# Hoja_principal_Sumo_2024.net
KiCad netlist of a schematic drawn in Altium Designer
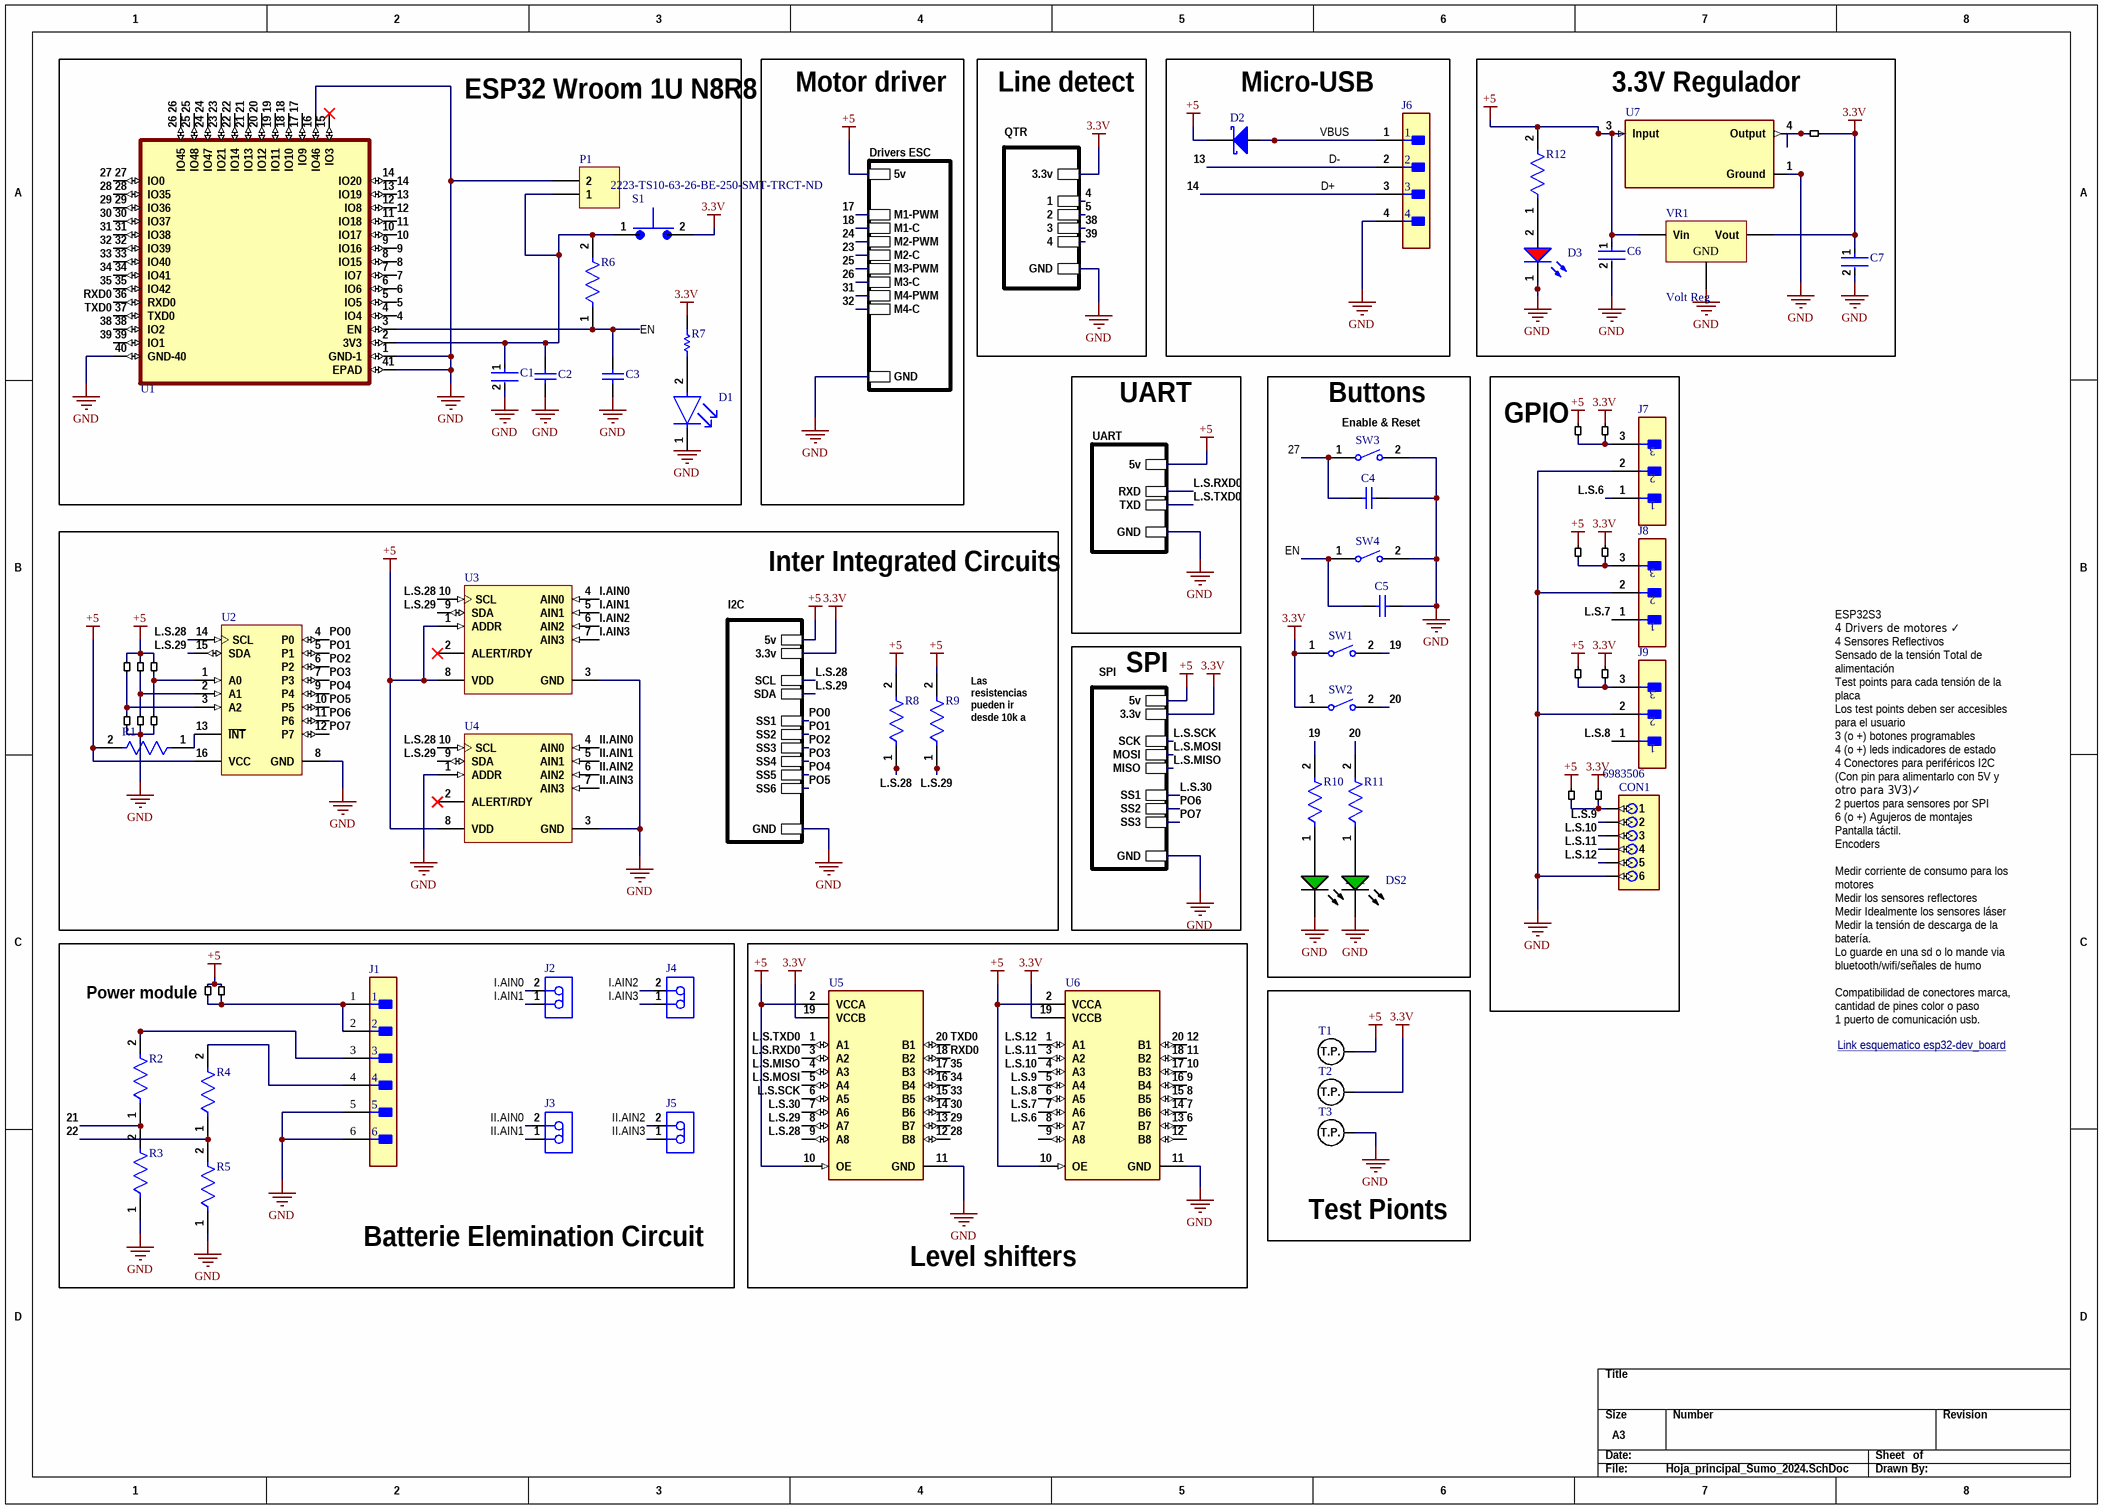
[diagram p0: Hoja_principal_Sumo_2024.SchDoc]

(export (version "E")
  (design (tool "Eeschema 10.0.6"))
  (components
    (comp (ref "C1")
      (value "TMK212BBJ106KG-T")
      (footprint "FP-0805-L_2_0_0_2-W_1_25-MFG")
      (description "Multilayer Ceramic Capacitor 10uF 25V X5R 10% SMD 0805 T/R")
      (fields (field (name "VOLTAGE") "16V") (field (name "TOLERANCE") "10%"))
      (libsource (lib "Altium Content Vault") (part "02cd4be3c70576c341d710602a673aa"))
    )
    (comp (ref "C2")
      (value "GRM21BR71H104KA01L")
      (footprint "CAPC2013X135X45ML10T25")
      (description "Chip Capacitor, 0.1 uF, +/- 10%, 50 V, -55 to 125 degC, 0805 (2012 Metric), RoHS, Tape and Reel")
      (fields (field (name "VOLTAGE") "50V") (field (name "TOLERANCE") "10%"))
      (libsource (lib "Altium Content Vault") (part "CAP-NP-2"))
    )
    (comp (ref "C3")
      (value "C0805C105K4PACTU")
      (footprint "CAPC2013X145X50LL20T25")
      (fields (field (name "MANUFACTURER") "Kemet"))
      (libsource (lib "Altium Content Vault") (part "CAP"))
    )
    (comp (ref "C4")
      (value "GRM21BR71H104KA01L")
      (footprint "CAPC2013X135X45ML10T25")
      (description "Chip Capacitor, 0.1 uF, +/- 10%, 50 V, -55 to 125 degC, 0805 (2012 Metric), RoHS, Tape and Reel")
      (fields (field (name "VOLTAGE") "50V") (field (name "TOLERANCE") "10%"))
      (libsource (lib "Altium Content Vault") (part "CAP-NP-2"))
    )
    (comp (ref "C5")
      (value "GRM21BR71H104KA01L")
      (footprint "CAPC2013X135X45ML10T25")
      (description "Chip Capacitor, 0.1 uF, +/- 10%, 50 V, -55 to 125 degC, 0805 (2012 Metric), RoHS, Tape and Reel")
      (fields (field (name "VOLTAGE") "50V") (field (name "TOLERANCE") "10%"))
      (libsource (lib "Altium Content Vault") (part "CAP-NP-2"))
    )
    (comp (ref "C6")
      (value "GRM31CR71A226KE15L")
      (footprint "FP-GRM31C-0_2-e0_3_0_8-MFG")
      (description "Chip Multilayer Ceramic Capacitors for General Purpose, 1206, 22uF, X7R, 15%, 10%, 10V")
      (fields (field (name "VOLTAGE") "10V") (field (name "TOLERANCE") "10%"))
      (libsource (lib "Altium Content Vault") (part "02cd4be3c70576c341d710602a673aa"))
    )
    (comp (ref "C7")
      (value "GRM31CR71A226KE15L")
      (footprint "FP-GRM31C-0_2-e0_3_0_8-MFG")
      (description "Chip Multilayer Ceramic Capacitors for General Purpose, 1206, 22uF, X7R, 15%, 10%, 10V")
      (fields (field (name "VOLTAGE") "10V") (field (name "TOLERANCE") "10%"))
      (libsource (lib "Altium Content Vault") (part "02cd4be3c70576c341d710602a673aa"))
    )
    (comp (ref "CON1")
      (value "B6B-ZR")
      (footprint "B6B-ZR")
      (description "Connector Header Surface Mount 6 position 0.059 (1.50mm)")
      (fields (field (name "MF") "JST") (field (name "SUPPLIER PART NUMBER 1") "6983506"))
      (libsource (lib "B6B-ZR") (part "B6B-ZR"))
    )
    (comp (ref "D1")
      (value "APHCM2012SYCK-F01")
      (footprint "FP-APHCM2012SYCK-F01-MFG")
      (description "LED YELLOW CLEAR CHIP SMD")
      (libsource (lib "Altium Content Vault") (part "8706943c75ba83719d021d2fdc84c58"))
    )
    (comp (ref "D2")
      (value "BAS3010A03WE6327HTSA1")
      (footprint "INF-SOD323_V")
      (description "Medium Power AF Schottky Diode, 0.41 V, 1 A, -65 to 125 degC, 2-Pin SOD323, RoHS, Tape and Reel")
      (fields (field (name "MANUFACTURER") "Infineon"))
      (libsource (lib "Altium Content Vault") (part "DSKY-KA-2"))
    )
    (comp (ref "D3")
      (value "150080SS75000")
      (footprint "WL-SMCW_0805_150080xx75000")
      (libsource (lib "Altium Content Vault") (part "LED_Red_2A-1K"))
    )
    (comp (ref "DS1")
      (value "HSMG-C170")
      (footprint "AVAG-HSMX-C170_V")
      (description "Chip LED, Green, 2.2 V, -40 to 85 degC, 2-Pin SMD, Pb-Free, Tape and Reel")
      (fields (field (name "MANUFACTURER") "Avago"))
      (libsource (lib "Altium Content Vault") (part "LED_GREEN_A1K2-2"))
    )
    (comp (ref "DS2")
      (value "HSMG-C170")
      (footprint "AVAG-HSMX-C170_V")
      (description "Chip LED, Green, 2.2 V, -40 to 85 degC, 2-Pin SMD, Pb-Free, Tape and Reel")
      (fields (field (name "MANUFACTURER") "Avago"))
      (libsource (lib "Altium Content Vault") (part "LED_GREEN_A1K2-2"))
    )
    (comp (ref "J1")
      (value "B6B-PH-K-K(LF)(SN)")
      (footprint "FP-B6B-PH-K-K_LF_SN-MFG")
      (description "PH Series 6 Position 2 mm Pitch Through Hole Top Entry Shrouded Header")
      (libsource (lib "Altium Content Vault") (part "f2cb566baf1c37ab5a3b8e90bbeafd6"))
    )
    (comp (ref "J2")
      (value "B2B-PH-K-S(LF)(SN)")
      (footprint "JST-B2B-PH-K-S_V")
      (fields (field (name "MANUFACTURER") "JST"))
      (libsource (lib "Altium Content Vault") (part "CN-2P-F-QF2"))
    )
    (comp (ref "J3")
      (value "B2B-PH-K-S(LF)(SN)")
      (footprint "JST-B2B-PH-K-S_V")
      (fields (field (name "MANUFACTURER") "JST"))
      (libsource (lib "Altium Content Vault") (part "CN-2P-F-QF2"))
    )
    (comp (ref "J4")
      (value "B2B-PH-K-S(LF)(SN)")
      (footprint "JST-B2B-PH-K-S_V")
      (fields (field (name "MANUFACTURER") "JST"))
      (libsource (lib "Altium Content Vault") (part "CN-2P-F-QF2"))
    )
    (comp (ref "J5")
      (value "B2B-PH-K-S(LF)(SN)")
      (footprint "JST-B2B-PH-K-S_V")
      (fields (field (name "MANUFACTURER") "JST"))
      (libsource (lib "Altium Content Vault") (part "CN-2P-F-QF2"))
    )
    (comp (ref "J6")
      (value "B4B-ZR(LF)(SN)")
      (footprint "FP-B4B-ZR_LF_SN-MFG")
      (description "CONN HEADER VERT 4POS 1.5MM")
      (libsource (lib "Altium Content Vault") (part "299a8cea1bdcbc3624fe62c390fa72c"))
    )
    (comp (ref "J7")
      (value "B3B-ZR(LF)(SN)")
      (footprint "FP-B3B-ZR_LF_SN-MFG")
      (description "CONN HEADER VERT 3POS 1.5MM")
      (libsource (lib "Altium Content Vault") (part "0d3f023dd272f625e17a2be33dea85f"))
    )
    (comp (ref "J8")
      (value "B3B-ZR(LF)(SN)")
      (footprint "FP-B3B-ZR_LF_SN-MFG")
      (description "CONN HEADER VERT 3POS 1.5MM")
      (libsource (lib "Altium Content Vault") (part "0d3f023dd272f625e17a2be33dea85f"))
    )
    (comp (ref "J9")
      (value "B3B-ZR(LF)(SN)")
      (footprint "FP-B3B-ZR_LF_SN-MFG")
      (description "CONN HEADER VERT 3POS 1.5MM")
      (libsource (lib "Altium Content Vault") (part "0d3f023dd272f625e17a2be33dea85f"))
    )
    (comp (ref "P1")
      (value "Header 2")
      (footprint "HDR1X2")
      (description "Header, 2-Pin")
      (fields (field (name "PUBLISHER") "Altium Limited"))
      (libsource (lib "Miscellaneous Connectors") (part "Header 2"))
    )
    (comp (ref "R1")
      (value "CRCW080510K0FKEA")
      (footprint "FP-CRCW0805-e3-IPC_A")
      (description "RES Thick Film, 10kΩ, 1%, 0.125W, 100ppm/°C, 0805")
      (fields (field (name "TOLERANCE") "1%"))
      (libsource (lib "Altium Content Vault") (part "1029c3af85768c4190bb7ad29bc67b5"))
    )
    (comp (ref "R2")
      (value "RC0805FR-07100KL")
      (footprint "FP-RC0805-0_6-IPC_C")
      (description "RES 100K OHM 1% 1/8W 0805")
      (fields (field (name "TOLERANCE") "1%"))
      (libsource (lib "Altium Content Vault") (part "1029c3af85768c4190bb7ad29bc67b5"))
    )
    (comp (ref "R3")
      (value "CRCW080547K0FKEA")
      (footprint "FP-CRCW0805-e3-MFG")
      (description "RES Thick Film, 47kΩ, 1%, 0.125W, 100ppm/°C, 0805")
      (fields (field (name "TOLERANCE") "1%"))
      (libsource (lib "Altium Content Vault") (part "1029c3af85768c4190bb7ad29bc67b5"))
    )
    (comp (ref "R4")
      (value "RC0805FR-07100KL")
      (footprint "FP-RC0805-0_6-IPC_C")
      (description "RES 100K OHM 1% 1/8W 0805")
      (fields (field (name "TOLERANCE") "1%"))
      (libsource (lib "Altium Content Vault") (part "1029c3af85768c4190bb7ad29bc67b5"))
    )
    (comp (ref "R5")
      (value "CRCW080547K0FKEA")
      (footprint "FP-CRCW0805-e3-MFG")
      (description "RES Thick Film, 47kΩ, 1%, 0.125W, 100ppm/°C, 0805")
      (fields (field (name "TOLERANCE") "1%"))
      (libsource (lib "Altium Content Vault") (part "1029c3af85768c4190bb7ad29bc67b5"))
    )
    (comp (ref "R6")
      (value "CRCW080510K0FKEA")
      (footprint "FP-CRCW0805-e3-IPC_A")
      (description "RES Thick Film, 10kΩ, 1%, 0.125W, 100ppm/°C, 0805")
      (fields (field (name "TOLERANCE") "1%"))
      (libsource (lib "Altium Content Vault") (part "1029c3af85768c4190bb7ad29bc67b5"))
    )
    (comp (ref "R7")
      (value "CRCW0805680RFKEA")
      (footprint "RESC2013X50X30NL20T20")
      (fields (field (name "MANUFACTURER") "Vishay Dale"))
      (libsource (lib "Altium Content Vault") (part "RES"))
    )
    (comp (ref "R8")
      (value "CRCW080510K0FKEA")
      (footprint "FP-CRCW0805-e3-IPC_A")
      (description "RES Thick Film, 10kΩ, 1%, 0.125W, 100ppm/°C, 0805")
      (fields (field (name "TOLERANCE") "1%"))
      (libsource (lib "Altium Content Vault") (part "1029c3af85768c4190bb7ad29bc67b5"))
    )
    (comp (ref "R9")
      (value "CRCW080510K0FKEA")
      (footprint "FP-CRCW0805-e3-IPC_A")
      (description "RES Thick Film, 10kΩ, 1%, 0.125W, 100ppm/°C, 0805")
      (fields (field (name "TOLERANCE") "1%"))
      (libsource (lib "Altium Content Vault") (part "1029c3af85768c4190bb7ad29bc67b5"))
    )
    (comp (ref "R10")
      (value "CRCW0805390RFKEA")
      (footprint "FP-CRCW0805-e3-IPC_B")
      (description "RES Thick Film, 390Ω, 1%, 0.125W, 100ppm/°C, 0805")
      (fields (field (name "TOLERANCE") "1%"))
      (libsource (lib "Altium Content Vault") (part "1029c3af85768c4190bb7ad29bc67b5"))
    )
    (comp (ref "R11")
      (value "CRCW0805390RFKEA")
      (footprint "FP-CRCW0805-e3-IPC_B")
      (description "RES Thick Film, 390Ω, 1%, 0.125W, 100ppm/°C, 0805")
      (fields (field (name "TOLERANCE") "1%"))
      (libsource (lib "Altium Content Vault") (part "1029c3af85768c4190bb7ad29bc67b5"))
    )
    (comp (ref "R12")
      (value "CRCW080510K0FKEA")
      (footprint "FP-CRCW0805-e3-IPC_A")
      (description "RES Thick Film, 10kΩ, 1%, 0.125W, 100ppm/°C, 0805")
      (fields (field (name "TOLERANCE") "1%"))
      (libsource (lib "Altium Content Vault") (part "1029c3af85768c4190bb7ad29bc67b5"))
    )
    (comp (ref "S1")
      (value "TS10-63-26-BE-250-SMT-TR")
      (footprint "SW_TS10-63-26-BE-250-SMT-TR")
      (fields (field (name "SUPPLIER PART NUMBER 1") "2223-TS10-63-26-BE-250-SMT-TRCT-ND"))
      (libsource (lib "TS10-63-26-BE-250-SMT-TR") (part "TS10-63-26-BE-250-SMT-TR"))
    )
    (comp (ref "SW1")
      (value "FSMSMTR")
      (footprint "TECO-FSMSMTR_V")
      (description "FSMSM Push Button Switch, 50 mA, -35 to 85 degC, 2-Pin SMD, RoHS, Tape and Reel")
      (fields (field (name "MANUFACTURER") "TE Connectivity"))
      (libsource (lib "Altium Content Vault") (part "SW-SPST-2_C"))
    )
    (comp (ref "SW2")
      (value "FSMSMTR")
      (footprint "TECO-FSMSMTR_V")
      (description "FSMSM Push Button Switch, 50 mA, -35 to 85 degC, 2-Pin SMD, RoHS, Tape and Reel")
      (fields (field (name "MANUFACTURER") "TE Connectivity"))
      (libsource (lib "Altium Content Vault") (part "SW-SPST-2_C"))
    )
    (comp (ref "SW3")
      (value "FSMSMTR")
      (footprint "TECO-FSMSMTR_V")
      (description "FSMSM Push Button Switch, 50 mA, -35 to 85 degC, 2-Pin SMD, RoHS, Tape and Reel")
      (fields (field (name "MANUFACTURER") "TE Connectivity"))
      (libsource (lib "Altium Content Vault") (part "SW-SPST-2_C"))
    )
    (comp (ref "SW4")
      (value "FSMSMTR")
      (footprint "TECO-FSMSMTR_V")
      (description "FSMSM Push Button Switch, 50 mA, -35 to 85 degC, 2-Pin SMD, RoHS, Tape and Reel")
      (fields (field (name "MANUFACTURER") "TE Connectivity"))
      (libsource (lib "Altium Content Vault") (part "SW-SPST-2_C"))
    )
    (comp (ref "T1")
      (value "Test point")
      (footprint "Testpoint")
      (libsource (lib "Schlib2") (part "Test point"))
    )
    (comp (ref "T2")
      (value "Test point")
      (footprint "Testpoint")
      (libsource (lib "Schlib2") (part "Test point"))
    )
    (comp (ref "T3")
      (value "Test point")
      (footprint "Testpoint")
      (libsource (lib "Schlib2") (part "Test point"))
    )
    (comp (ref "U1")
      (value "ESP32-S3-WROOM-1 N8R8")
      (footprint "PCBComponent_1")
      (description "SMD MODULE, ESP32-S3R8 WITH 8 MB")
      (fields (field (name "MF") "Espressif Systems") (field (name "MP") "ESP32-S3-WROOM-1"))
      (libsource (lib "ESP32-S3-WROOM-1") (part "ESP32-S3-WROOM-1"))
    )
    (comp (ref "U2")
      (value "PCF8574DWR")
      (footprint "DW0016A_L")
      (fields (field (name "MANUFACTURER") "Texas Instruments"))
      (libsource (lib "Altium Content Vault") (part "TI-PCF8574-SOIC_DW-16"))
    )
    (comp (ref "U3")
      (value "ADS1115IDGST")
      (footprint "TI-DGS10_N")
      (fields (field (name "MANUFACTURER") "Texas Instruments"))
      (libsource (lib "Altium Content Vault") (part "TI-ADS1015_1115-10"))
    )
    (comp (ref "U4")
      (value "ADS1115IDGST")
      (footprint "TI-DGS10_N")
      (fields (field (name "MANUFACTURER") "Texas Instruments"))
      (libsource (lib "Altium Content Vault") (part "TI-ADS1015_1115-10"))
    )
    (comp (ref "U5")
      (value "TXS0108EQPWRQ1")
      (footprint "FP-PW0020A-MFG")
      (description "IC TRNSLTR BIDIRECTIONAL 20TSSOP")
      (fields
        (field (name "OCTOPART") "https://octopart.com/txs0108eqpwrq1-texas+instruments-59160487")
        (field (name "MANUFACTURER") "Texas Instruments")
      )
      (libsource (lib "Altium Content Vault") (part "b852cf3f2c97e4a3d4172ee3f19d589"))
    )
    (comp (ref "U6")
      (value "TXS0108EQPWRQ1")
      (footprint "FP-PW0020A-MFG")
      (description "IC TRNSLTR BIDIRECTIONAL 20TSSOP")
      (fields
        (field (name "OCTOPART") "https://octopart.com/txs0108eqpwrq1-texas+instruments-59160487")
        (field (name "MANUFACTURER") "Texas Instruments")
      )
      (libsource (lib "Altium Content Vault") (part "b852cf3f2c97e4a3d4172ee3f19d589"))
    )
    (comp (ref "U7")
      (value "NCP1117DT33T5G")
      (footprint "FP-369C-MFG")
      (description "IC REG LINEAR 3.3V 1A DPAK")
      (libsource (lib "Altium Content Vault") (part "f1512ae604efdd4bd306cab1b45f420"))
    )
    (comp (ref "VR1")
      (value "Volt Reg")
      (footprint "TO-220AB")
      (description "Voltage Regulator")
      (fields (field (name "PUBLISHER") "Altium Limited"))
      (libsource (lib "Miscellaneous Devices") (part "Volt Reg"))
    )
    (comp (ref "W1") (value "Jumper") (footprint "Jumper Mini") (libsource (lib "Schlib1") (part "Jumper")))
    (comp (ref "W2") (value "Jumper") (footprint "Jumper Mini") (libsource (lib "Schlib1") (part "Jumper")))
    (comp (ref "W3") (value "Jumper") (footprint "Jumper Mini") (libsource (lib "Schlib1") (part "Jumper")))
    (comp (ref "W4") (value "Jumper") (footprint "Jumper Mini") (libsource (lib "Schlib1") (part "Jumper")))
    (comp (ref "W5") (value "Jumper") (footprint "Jumper Mini") (libsource (lib "Schlib1") (part "Jumper")))
    (comp (ref "W6") (value "Jumper") (footprint "Jumper Mini") (libsource (lib "Schlib1") (part "Jumper")))
    (comp (ref "W7") (value "Jumper") (footprint "Jumper Mid") (libsource (lib "Schlib1") (part "Jumper")))
    (comp (ref "W8") (value "Jumper") (footprint "Jumper Mid") (libsource (lib "Schlib1") (part "Jumper")))
    (comp (ref "W9") (value "Jumper") (footprint "Jumper Mid") (libsource (lib "Schlib1") (part "Jumper")))
    (comp (ref "W10") (value "Jumper") (footprint "Jumper Mid") (libsource (lib "Schlib1") (part "Jumper")))
    (comp (ref "W11") (value "Jumper") (footprint "Jumper Mid") (libsource (lib "Schlib1") (part "Jumper")))
    (comp (ref "W12") (value "Jumper") (footprint "Jumper Mid") (libsource (lib "Schlib1") (part "Jumper")))
    (comp (ref "W13") (value "Jumper") (footprint "Jumper Mid") (libsource (lib "Schlib1") (part "Jumper")))
    (comp (ref "W14") (value "Jumper") (footprint "Jumper Mid") (libsource (lib "Schlib1") (part "Jumper")))
    (comp (ref "W15") (value "Jumper") (footprint "Jumper Mid") (libsource (lib "Schlib1") (part "Jumper")))
    (comp (ref "W16") (value "Jumper") (footprint "Jumper Mid") (libsource (lib "Schlib1") (part "Jumper")))
    (comp (ref "W17") (value "Jumper") (footprint "Jumper Mid") (libsource (lib "Schlib1") (part "Jumper")))
  )
  (nets
    (net (code "1") (name "+5") (class "Default")
      (node (ref "C6") (pin "1") (pinfunction "1_1") (pintype "passive"))
      (node (ref "D2") (pin "1") (pinfunction "K_1") (pintype "passive"))
      (node (ref "R1") (pin "2") (pinfunction "2_2") (pintype "passive"))
      (node (ref "R12") (pin "2") (pinfunction "2_2") (pintype "passive"))
      (node (ref "R8") (pin "2") (pinfunction "2_2") (pintype "passive"))
      (node (ref "R9") (pin "2") (pinfunction "2_2") (pintype "passive"))
      (node (ref "T1") (pin "1") (pinfunction "T.P._1") (pintype "passive"))
      (node (ref "U2") (pin "16") (pinfunction "VCC_16") (pintype "power_in"))
      (node (ref "U3") (pin "1") (pinfunction "ADDR_1") (pintype "input"))
      (node (ref "U3") (pin "8") (pinfunction "VDD_8") (pintype "power_in"))
      (node (ref "U4") (pin "8") (pinfunction "VDD_8") (pintype "power_in"))
      (node (ref "U5") (pin "10") (pinfunction "OE_10") (pintype "input"))
      (node (ref "U5") (pin "2") (pinfunction "VCCA_2") (pintype "power_in"))
      (node (ref "U6") (pin "10") (pinfunction "OE_10") (pintype "input"))
      (node (ref "U6") (pin "2") (pinfunction "VCCA_2") (pintype "power_in"))
      (node (ref "U7") (pin "3") (pinfunction "Input_3") (pintype "input"))
      (node (ref "VR1") (pin "3") (pinfunction "Vin_3") (pintype "passive"))
      (node (ref "W1") (pin "2") (pinfunction "2_2") (pintype "passive"))
      (node (ref "W10") (pin "2") (pinfunction "2_2") (pintype "passive"))
      (node (ref "W11") (pin "2") (pinfunction "2_2") (pintype "passive"))
      (node (ref "W12") (pin "2") (pinfunction "2_2") (pintype "passive"))
      (node (ref "W3") (pin "2") (pinfunction "2_2") (pintype "passive"))
      (node (ref "W5") (pin "2") (pinfunction "2_2") (pintype "passive"))
      (node (ref "W7") (pin "2") (pinfunction "2_2") (pintype "passive"))
      (node (ref "W8") (pin "2") (pinfunction "2_2") (pintype "passive"))
      (node (ref "W9") (pin "2") (pinfunction "2_2") (pintype "passive"))
    )
    (net (code "2") (name "/4") (class "Default")
      (node (ref "U1") (pin "4") (pinfunction "IO4_4") (pintype "bidirectional"))
    )
    (net (code "3") (name "/5") (class "Default")
      (node (ref "U1") (pin "5") (pinfunction "IO5_5") (pintype "bidirectional"))
    )
    (net (code "4") (name "/6") (class "Default")
      (node (ref "U1") (pin "6") (pinfunction "IO6_6") (pintype "bidirectional"))
      (node (ref "U6") (pin "13") (pinfunction "B7_13") (pintype "bidirectional"))
    )
    (net (code "5") (name "/7") (class "Default")
      (node (ref "U1") (pin "7") (pinfunction "IO7_7") (pintype "bidirectional"))
      (node (ref "U6") (pin "14") (pinfunction "B6_14") (pintype "bidirectional"))
    )
    (net (code "6") (name "/8") (class "Default")
      (node (ref "U1") (pin "8") (pinfunction "IO15_8") (pintype "bidirectional"))
      (node (ref "U6") (pin "15") (pinfunction "B5_15") (pintype "bidirectional"))
    )
    (net (code "7") (name "/9") (class "Default")
      (node (ref "U1") (pin "9") (pinfunction "IO16_9") (pintype "bidirectional"))
      (node (ref "U6") (pin "16") (pinfunction "B4_16") (pintype "bidirectional"))
    )
    (net (code "8") (name "/10") (class "Default")
      (node (ref "U1") (pin "10") (pinfunction "IO17_10") (pintype "bidirectional"))
      (node (ref "U6") (pin "17") (pinfunction "B3_17") (pintype "bidirectional"))
    )
    (net (code "9") (name "/11") (class "Default")
      (node (ref "U1") (pin "11") (pinfunction "IO18_11") (pintype "bidirectional"))
      (node (ref "U6") (pin "18") (pinfunction "B2_18") (pintype "bidirectional"))
    )
    (net (code "10") (name "/12") (class "Default")
      (node (ref "U1") (pin "12") (pinfunction "IO8_12") (pintype "bidirectional"))
      (node (ref "U6") (pin "20") (pinfunction "B1_20") (pintype "bidirectional"))
    )
    (net (code "11") (name "/13") (class "Default")
      (node (ref "J6") (pin "2") (pinfunction "2_2") (pintype "passive"))
      (node (ref "U1") (pin "13") (pinfunction "IO19_13") (pintype "bidirectional"))
    )
    (net (code "12") (name "/14") (class "Default")
      (node (ref "J6") (pin "3") (pinfunction "3_3") (pintype "passive"))
      (node (ref "U1") (pin "14") (pinfunction "IO20_14") (pintype "bidirectional"))
    )
    (net (code "13") (name "/17") (class "Default")
      (node (ref "U1") (pin "17") (pinfunction "IO9_17") (pintype "bidirectional"))
    )
    (net (code "14") (name "/18") (class "Default")
      (node (ref "U1") (pin "18") (pinfunction "IO10_18") (pintype "bidirectional"))
    )
    (net (code "15") (name "/19") (class "Default")
      (node (ref "R10") (pin "2") (pinfunction "2_2") (pintype "passive"))
      (node (ref "SW1") (pin "2") (pinfunction "2_2") (pintype "passive"))
      (node (ref "U1") (pin "19") (pinfunction "IO11_19") (pintype "bidirectional"))
    )
    (net (code "16") (name "/20") (class "Default")
      (node (ref "R11") (pin "2") (pinfunction "2_2") (pintype "passive"))
      (node (ref "SW2") (pin "2") (pinfunction "2_2") (pintype "passive"))
      (node (ref "U1") (pin "20") (pinfunction "IO12_20") (pintype "bidirectional"))
    )
    (net (code "17") (name "/21") (class "Default")
      (node (ref "R2") (pin "1") (pinfunction "1_1") (pintype "passive"))
      (node (ref "R3") (pin "2") (pinfunction "2_2") (pintype "passive"))
      (node (ref "U1") (pin "21") (pinfunction "IO13_21") (pintype "bidirectional"))
    )
    (net (code "18") (name "/22") (class "Default")
      (node (ref "R4") (pin "1") (pinfunction "1_1") (pintype "passive"))
      (node (ref "R5") (pin "2") (pinfunction "2_2") (pintype "passive"))
      (node (ref "U1") (pin "22") (pinfunction "IO14_22") (pintype "bidirectional"))
    )
    (net (code "19") (name "/23") (class "Default")
      (node (ref "U1") (pin "23") (pinfunction "IO21_23") (pintype "bidirectional"))
    )
    (net (code "20") (name "/24") (class "Default")
      (node (ref "U1") (pin "24") (pinfunction "IO47_24") (pintype "bidirectional"))
    )
    (net (code "21") (name "/25") (class "Default")
      (node (ref "U1") (pin "25") (pinfunction "IO48_25") (pintype "bidirectional"))
    )
    (net (code "22") (name "/26") (class "Default")
      (node (ref "U1") (pin "26") (pinfunction "IO45_26") (pintype "bidirectional"))
    )
    (net (code "23") (name "/27") (class "Default")
      (node (ref "C4") (pin "2") (pinfunction "2_2") (pintype "passive"))
      (node (ref "SW3") (pin "1") (pinfunction "1_1") (pintype "passive"))
      (node (ref "U1") (pin "27") (pinfunction "IO0_27") (pintype "bidirectional"))
    )
    (net (code "24") (name "/28") (class "Default")
      (node (ref "U1") (pin "28") (pinfunction "IO35_28") (pintype "bidirectional"))
      (node (ref "U5") (pin "12") (pinfunction "B8_12") (pintype "bidirectional"))
    )
    (net (code "25") (name "/29") (class "Default")
      (node (ref "U1") (pin "29") (pinfunction "IO36_29") (pintype "bidirectional"))
      (node (ref "U5") (pin "13") (pinfunction "B7_13") (pintype "bidirectional"))
    )
    (net (code "26") (name "/30") (class "Default")
      (node (ref "U1") (pin "30") (pinfunction "IO37_30") (pintype "bidirectional"))
      (node (ref "U5") (pin "14") (pinfunction "B6_14") (pintype "bidirectional"))
    )
    (net (code "27") (name "/31") (class "Default")
      (node (ref "U1") (pin "31") (pinfunction "IO38_31") (pintype "bidirectional"))
    )
    (net (code "28") (name "/32") (class "Default")
      (node (ref "U1") (pin "32") (pinfunction "IO39_32") (pintype "bidirectional"))
    )
    (net (code "29") (name "/33") (class "Default")
      (node (ref "U1") (pin "33") (pinfunction "IO40_33") (pintype "bidirectional"))
      (node (ref "U5") (pin "15") (pinfunction "B5_15") (pintype "bidirectional"))
    )
    (net (code "30") (name "/34") (class "Default")
      (node (ref "U1") (pin "34") (pinfunction "IO41_34") (pintype "bidirectional"))
      (node (ref "U5") (pin "16") (pinfunction "B4_16") (pintype "bidirectional"))
    )
    (net (code "31") (name "/35") (class "Default")
      (node (ref "U1") (pin "35") (pinfunction "IO42_35") (pintype "bidirectional"))
      (node (ref "U5") (pin "17") (pinfunction "B3_17") (pintype "bidirectional"))
    )
    (net (code "32") (name "/38") (class "Default")
      (node (ref "U1") (pin "38") (pinfunction "IO2_38") (pintype "bidirectional"))
    )
    (net (code "33") (name "/39") (class "Default")
      (node (ref "U1") (pin "39") (pinfunction "IO1_39") (pintype "bidirectional"))
    )
    (net (code "34") (name "/EN") (class "Default")
      (node (ref "C3") (pin "2") (pinfunction "2_2") (pintype "passive"))
      (node (ref "C5") (pin "2") (pinfunction "2_2") (pintype "passive"))
      (node (ref "R6") (pin "1") (pinfunction "1_1") (pintype "passive"))
      (node (ref "SW4") (pin "1") (pinfunction "1_1") (pintype "passive"))
      (node (ref "U1") (pin "3") (pinfunction "EN_3") (pintype "bidirectional"))
    )
    (net (code "35") (name "/I.AIN0") (class "Default")
      (node (ref "J2") (pin "2") (pinfunction "2_2") (pintype "passive"))
      (node (ref "U3") (pin "4") (pinfunction "AIN0_4") (pintype "input"))
    )
    (net (code "36") (name "/I.AIN1") (class "Default")
      (node (ref "J2") (pin "1") (pinfunction "1_1") (pintype "passive"))
      (node (ref "U3") (pin "5") (pinfunction "AIN1_5") (pintype "input"))
    )
    (net (code "37") (name "/I.AIN2") (class "Default")
      (node (ref "J4") (pin "2") (pinfunction "2_2") (pintype "passive"))
      (node (ref "U3") (pin "6") (pinfunction "AIN2_6") (pintype "input"))
    )
    (net (code "38") (name "/I.AIN3") (class "Default")
      (node (ref "J4") (pin "1") (pinfunction "1_1") (pintype "passive"))
      (node (ref "U3") (pin "7") (pinfunction "AIN3_7") (pintype "input"))
    )
    (net (code "39") (name "/II.AIN0") (class "Default")
      (node (ref "J3") (pin "2") (pinfunction "2_2") (pintype "passive"))
      (node (ref "U4") (pin "4") (pinfunction "AIN0_4") (pintype "input"))
    )
    (net (code "40") (name "/II.AIN1") (class "Default")
      (node (ref "J3") (pin "1") (pinfunction "1_1") (pintype "passive"))
      (node (ref "U4") (pin "5") (pinfunction "AIN1_5") (pintype "input"))
    )
    (net (code "41") (name "/II.AIN2") (class "Default")
      (node (ref "J5") (pin "2") (pinfunction "2_2") (pintype "passive"))
      (node (ref "U4") (pin "6") (pinfunction "AIN2_6") (pintype "input"))
    )
    (net (code "42") (name "/II.AIN3") (class "Default")
      (node (ref "J5") (pin "1") (pinfunction "1_1") (pintype "passive"))
      (node (ref "U4") (pin "7") (pinfunction "AIN3_7") (pintype "input"))
    )
    (net (code "43") (name "/L.S.6") (class "Default")
      (node (ref "J7") (pin "1") (pinfunction "1_1") (pintype "passive"))
      (node (ref "U6") (pin "8") (pinfunction "A7_8") (pintype "bidirectional"))
    )
    (net (code "44") (name "/L.S.7") (class "Default")
      (node (ref "J8") (pin "1") (pinfunction "1_1") (pintype "passive"))
      (node (ref "U6") (pin "7") (pinfunction "A6_7") (pintype "bidirectional"))
    )
    (net (code "45") (name "/L.S.8") (class "Default")
      (node (ref "J9") (pin "1") (pinfunction "1_1") (pintype "passive"))
      (node (ref "U6") (pin "6") (pinfunction "A5_6") (pintype "bidirectional"))
    )
    (net (code "46") (name "/L.S.9") (class "Default")
      (node (ref "CON1") (pin "2") (pinfunction "2_2") (pintype "bidirectional"))
      (node (ref "U6") (pin "5") (pinfunction "A4_5") (pintype "bidirectional"))
    )
    (net (code "47") (name "/L.S.10") (class "Default")
      (node (ref "CON1") (pin "3") (pinfunction "3_3") (pintype "bidirectional"))
      (node (ref "U6") (pin "4") (pinfunction "A3_4") (pintype "bidirectional"))
    )
    (net (code "48") (name "/L.S.11") (class "Default")
      (node (ref "CON1") (pin "4") (pinfunction "4_4") (pintype "bidirectional"))
      (node (ref "U6") (pin "3") (pinfunction "A2_3") (pintype "bidirectional"))
    )
    (net (code "49") (name "/L.S.12") (class "Default")
      (node (ref "CON1") (pin "5") (pinfunction "5_5") (pintype "bidirectional"))
      (node (ref "U6") (pin "1") (pinfunction "A1_1") (pintype "bidirectional"))
    )
    (net (code "50") (name "/L.S.28") (class "Default")
      (node (ref "R8") (pin "1") (pinfunction "1_1") (pintype "passive"))
      (node (ref "U2") (pin "14") (pinfunction "SCL_14") (pintype "input"))
      (node (ref "U3") (pin "10") (pinfunction "SCL_10") (pintype "input"))
      (node (ref "U4") (pin "10") (pinfunction "SCL_10") (pintype "input"))
      (node (ref "U5") (pin "9") (pinfunction "A8_9") (pintype "bidirectional"))
    )
    (net (code "51") (name "/L.S.29") (class "Default")
      (node (ref "R9") (pin "1") (pinfunction "1_1") (pintype "passive"))
      (node (ref "U2") (pin "15") (pinfunction "SDA_15") (pintype "bidirectional"))
      (node (ref "U3") (pin "9") (pinfunction "SDA_9") (pintype "bidirectional"))
      (node (ref "U4") (pin "9") (pinfunction "SDA_9") (pintype "bidirectional"))
      (node (ref "U5") (pin "8") (pinfunction "A7_8") (pintype "bidirectional"))
    )
    (net (code "52") (name "/L.S.30") (class "Default")
      (node (ref "U5") (pin "7") (pinfunction "A6_7") (pintype "bidirectional"))
    )
    (net (code "53") (name "/L.S.MISO") (class "Default")
      (node (ref "U5") (pin "4") (pinfunction "A3_4") (pintype "bidirectional"))
    )
    (net (code "54") (name "/L.S.MOSI") (class "Default")
      (node (ref "U5") (pin "5") (pinfunction "A4_5") (pintype "bidirectional"))
    )
    (net (code "55") (name "/L.S.RXD0") (class "Default")
      (node (ref "U5") (pin "3") (pinfunction "A2_3") (pintype "bidirectional"))
    )
    (net (code "56") (name "/L.S.SCK") (class "Default")
      (node (ref "U5") (pin "6") (pinfunction "A5_6") (pintype "bidirectional"))
    )
    (net (code "57") (name "/L.S.TXD0") (class "Default")
      (node (ref "U5") (pin "1") (pinfunction "A1_1") (pintype "bidirectional"))
    )
    (net (code "58") (name "/PO0") (class "Default")
      (node (ref "U2") (pin "4") (pinfunction "P0_4") (pintype "bidirectional"))
    )
    (net (code "59") (name "/PO1") (class "Default")
      (node (ref "U2") (pin "5") (pinfunction "P1_5") (pintype "bidirectional"))
    )
    (net (code "60") (name "/PO2") (class "Default")
      (node (ref "U2") (pin "6") (pinfunction "P2_6") (pintype "bidirectional"))
    )
    (net (code "61") (name "/PO3") (class "Default")
      (node (ref "U2") (pin "7") (pinfunction "P3_7") (pintype "bidirectional"))
    )
    (net (code "62") (name "/PO4") (class "Default")
      (node (ref "U2") (pin "9") (pinfunction "P4_9") (pintype "bidirectional"))
    )
    (net (code "63") (name "/PO5") (class "Default")
      (node (ref "U2") (pin "10") (pinfunction "P5_10") (pintype "bidirectional"))
    )
    (net (code "64") (name "/PO6") (class "Default")
      (node (ref "U2") (pin "11") (pinfunction "P6_11") (pintype "bidirectional"))
    )
    (net (code "65") (name "/PO7") (class "Default")
      (node (ref "U2") (pin "12") (pinfunction "P7_12") (pintype "bidirectional"))
    )
    (net (code "66") (name "/RXD0") (class "Default")
      (node (ref "U1") (pin "36") (pinfunction "RXD0_36") (pintype "bidirectional"))
      (node (ref "U5") (pin "18") (pinfunction "B2_18") (pintype "bidirectional"))
    )
    (net (code "67") (name "/TXD0") (class "Default")
      (node (ref "U1") (pin "37") (pinfunction "TXD0_37") (pintype "bidirectional"))
      (node (ref "U5") (pin "20") (pinfunction "B1_20") (pintype "bidirectional"))
    )
    (net (code "68") (name "/VBUS") (class "Default")
      (node (ref "D2") (pin "2") (pinfunction "A_2") (pintype "passive"))
      (node (ref "J6") (pin "1") (pinfunction "1_1") (pintype "passive"))
    )
    (net (code "69") (name "3.3V") (class "Default")
      (node (ref "C7") (pin "1") (pinfunction "1_1") (pintype "passive"))
      (node (ref "R7") (pin "2") (pinfunction "2_2") (pintype "passive"))
      (node (ref "S1") (pin "2") (pinfunction "2_2") (pintype "passive"))
      (node (ref "SW1") (pin "1") (pinfunction "1_1") (pintype "passive"))
      (node (ref "SW2") (pin "1") (pinfunction "1_1") (pintype "passive"))
      (node (ref "T2") (pin "1") (pinfunction "T.P._1") (pintype "passive"))
      (node (ref "U5") (pin "19") (pinfunction "VCCB_19") (pintype "power_in"))
      (node (ref "U6") (pin "19") (pinfunction "VCCB_19") (pintype "power_in"))
      (node (ref "VR1") (pin "2") (pinfunction "Vout_2") (pintype "passive"))
      (node (ref "W13") (pin "2") (pinfunction "2_2") (pintype "passive"))
      (node (ref "W14") (pin "2") (pinfunction "2_2") (pintype "passive"))
      (node (ref "W15") (pin "2") (pinfunction "2_2") (pintype "passive"))
      (node (ref "W16") (pin "2") (pinfunction "2_2") (pintype "passive"))
      (node (ref "W17") (pin "1") (pinfunction "1_1") (pintype "passive"))
    )
    (net (code "70") (name "GND") (class "Default")
      (node (ref "C1") (pin "2") (pinfunction "2_2") (pintype "passive"))
      (node (ref "C2") (pin "2") (pinfunction "2_2") (pintype "passive"))
      (node (ref "C3") (pin "1") (pinfunction "1_1") (pintype "passive"))
      (node (ref "C4") (pin "1") (pinfunction "1_1") (pintype "passive"))
      (node (ref "C5") (pin "1") (pinfunction "1_1") (pintype "passive"))
      (node (ref "C6") (pin "2") (pinfunction "2_2") (pintype "passive"))
      (node (ref "C7") (pin "2") (pinfunction "2_2") (pintype "passive"))
      (node (ref "CON1") (pin "6") (pinfunction "6_6") (pintype "bidirectional"))
      (node (ref "D3") (pin "1") (pinfunction "K_1") (pintype "passive"))
      (node (ref "DS1") (pin "2") (pinfunction "K_2") (pintype "passive"))
      (node (ref "DS2") (pin "2") (pinfunction "K_2") (pintype "passive"))
      (node (ref "J1") (pin "5") (pinfunction "5_5") (pintype "passive"))
      (node (ref "J1") (pin "6") (pinfunction "6_6") (pintype "passive"))
      (node (ref "J6") (pin "4") (pinfunction "4_4") (pintype "passive"))
      (node (ref "J7") (pin "2") (pinfunction "2_2") (pintype "passive"))
      (node (ref "J8") (pin "2") (pinfunction "2_2") (pintype "passive"))
      (node (ref "J9") (pin "2") (pinfunction "2_2") (pintype "passive"))
      (node (ref "P1") (pin "2") (pinfunction "2_2") (pintype "passive"))
      (node (ref "R3") (pin "1") (pinfunction "1_1") (pintype "passive"))
      (node (ref "R5") (pin "1") (pinfunction "1_1") (pintype "passive"))
      (node (ref "SW3") (pin "2") (pinfunction "2_2") (pintype "passive"))
      (node (ref "SW4") (pin "2") (pinfunction "2_2") (pintype "passive"))
      (node (ref "T3") (pin "1") (pinfunction "T.P._1") (pintype "passive"))
      (node (ref "U1") (pin "1") (pinfunction "GND-1_1") (pintype "bidirectional"))
      (node (ref "U1") (pin "16") (pinfunction "IO46_16") (pintype "bidirectional"))
      (node (ref "U1") (pin "40") (pinfunction "GND-40_40") (pintype "bidirectional"))
      (node (ref "U1") (pin "41") (pinfunction "EPAD_41") (pintype "bidirectional"))
      (node (ref "U2") (pin "8") (pinfunction "GND_8") (pintype "power_in"))
      (node (ref "U3") (pin "3") (pinfunction "GND_3") (pintype "power_in"))
      (node (ref "U4") (pin "1") (pinfunction "ADDR_1") (pintype "input"))
      (node (ref "U4") (pin "3") (pinfunction "GND_3") (pintype "power_in"))
      (node (ref "U5") (pin "11") (pinfunction "GND_11") (pintype "power_in"))
      (node (ref "U6") (pin "11") (pinfunction "GND_11") (pintype "power_in"))
      (node (ref "U7") (pin "1") (pinfunction "Ground_1") (pintype "power_in"))
      (node (ref "VR1") (pin "1") (pinfunction "GND_1") (pintype "passive"))
      (node (ref "W2") (pin "1") (pinfunction "1_1") (pintype "passive"))
      (node (ref "W4") (pin "1") (pinfunction "1_1") (pintype "passive"))
      (node (ref "W6") (pin "1") (pinfunction "1_1") (pintype "passive"))
    )
    (net (code "71") (name "Net-(CON1-Pad1)") (class "Default")
      (node (ref "CON1") (pin "1") (pinfunction "1_1") (pintype "bidirectional"))
      (node (ref "W13") (pin "1") (pinfunction "1_1") (pintype "passive"))
      (node (ref "W9") (pin "1") (pinfunction "1_1") (pintype "passive"))
    )
    (net (code "72") (name "Net-(D1-A)") (class "Default")
      (node (ref "D1") (pin "2") (pinfunction "A_2") (pintype "passive"))
      (node (ref "R7") (pin "1") (pinfunction "1_1") (pintype "passive"))
    )
    (net (code "73") (name "Net-(D3-A)") (class "Default")
      (node (ref "D3") (pin "2") (pinfunction "A_2") (pintype "passive"))
      (node (ref "R12") (pin "1") (pinfunction "1_1") (pintype "passive"))
    )
    (net (code "74") (name "Net-(DS1-A)") (class "Default")
      (node (ref "DS1") (pin "1") (pinfunction "A_1") (pintype "passive"))
      (node (ref "R10") (pin "1") (pinfunction "1_1") (pintype "passive"))
    )
    (net (code "75") (name "Net-(DS2-A)") (class "Default")
      (node (ref "DS2") (pin "1") (pinfunction "A_1") (pintype "passive"))
      (node (ref "R11") (pin "1") (pinfunction "1_1") (pintype "passive"))
    )
    (net (code "76") (name "Net-(J1-Pad1)") (class "Default")
      (node (ref "J1") (pin "1") (pinfunction "1_1") (pintype "passive"))
      (node (ref "J1") (pin "2") (pinfunction "2_2") (pintype "passive"))
      (node (ref "W7") (pin "1") (pinfunction "1_1") (pintype "passive"))
      (node (ref "W8") (pin "1") (pinfunction "1_1") (pintype "passive"))
    )
    (net (code "77") (name "Net-(J1-Pad3)") (class "Default")
      (node (ref "J1") (pin "3") (pinfunction "3_3") (pintype "passive"))
      (node (ref "R2") (pin "2") (pinfunction "2_2") (pintype "passive"))
    )
    (net (code "78") (name "Net-(J1-Pad4)") (class "Default")
      (node (ref "J1") (pin "4") (pinfunction "4_4") (pintype "passive"))
      (node (ref "R4") (pin "2") (pinfunction "2_2") (pintype "passive"))
    )
    (net (code "79") (name "Net-(J7-Pad3)") (class "Default")
      (node (ref "J7") (pin "3") (pinfunction "3_3") (pintype "passive"))
      (node (ref "W10") (pin "1") (pinfunction "1_1") (pintype "passive"))
      (node (ref "W14") (pin "1") (pinfunction "1_1") (pintype "passive"))
    )
    (net (code "80") (name "Net-(J8-Pad3)") (class "Default")
      (node (ref "J8") (pin "3") (pinfunction "3_3") (pintype "passive"))
      (node (ref "W11") (pin "1") (pinfunction "1_1") (pintype "passive"))
      (node (ref "W15") (pin "1") (pinfunction "1_1") (pintype "passive"))
    )
    (net (code "81") (name "Net-(J9-Pad3)") (class "Default")
      (node (ref "J9") (pin "3") (pinfunction "3_3") (pintype "passive"))
      (node (ref "W12") (pin "1") (pinfunction "1_1") (pintype "passive"))
      (node (ref "W16") (pin "1") (pinfunction "1_1") (pintype "passive"))
    )
    (net (code "82") (name "Net-(U1-3V3)") (class "Default")
      (node (ref "C1") (pin "1") (pinfunction "1_1") (pintype "passive"))
      (node (ref "C2") (pin "1") (pinfunction "1_1") (pintype "passive"))
      (node (ref "P1") (pin "1") (pinfunction "1_1") (pintype "passive"))
      (node (ref "R6") (pin "2") (pinfunction "2_2") (pintype "passive"))
      (node (ref "S1") (pin "1") (pinfunction "1_1") (pintype "passive"))
      (node (ref "U1") (pin "2") (pinfunction "3V3_2") (pintype "bidirectional"))
    )
    (net (code "83") (name "Net-(U2-A0)") (class "Default")
      (node (ref "U2") (pin "1") (pinfunction "A0_1") (pintype "input"))
      (node (ref "W5") (pin "1") (pinfunction "1_1") (pintype "passive"))
      (node (ref "W6") (pin "2") (pinfunction "2_2") (pintype "passive"))
    )
    (net (code "84") (name "Net-(U2-A1)") (class "Default")
      (node (ref "U2") (pin "2") (pinfunction "A1_2") (pintype "input"))
      (node (ref "W3") (pin "1") (pinfunction "1_1") (pintype "passive"))
      (node (ref "W4") (pin "2") (pinfunction "2_2") (pintype "passive"))
    )
    (net (code "85") (name "Net-(U2-A2)") (class "Default")
      (node (ref "U2") (pin "3") (pinfunction "A2_3") (pintype "input"))
      (node (ref "W1") (pin "1") (pinfunction "1_1") (pintype "passive"))
      (node (ref "W2") (pin "2") (pinfunction "2_2") (pintype "passive"))
    )
    (net (code "86") (name "Net-(U2-~{INT})") (class "Default")
      (node (ref "R1") (pin "1") (pinfunction "1_1") (pintype "passive"))
      (node (ref "U2") (pin "13") (pinfunction "~{INT}_13") (pintype "open_collector"))
    )
    (net (code "87") (name "Net-(U7-Output)") (class "Default")
      (node (ref "U7") (pin "4") (pinfunction "Output_4") (pintype "output"))
      (node (ref "W17") (pin "2") (pinfunction "2_2") (pintype "passive"))
    )
    (net (code "88") (name "unconnected-(D1-C-Pad1)") (class "Default")
      (node (ref "D1") (pin "1") (pinfunction "C_1") (pintype "passive"))
    )
    (net (code "89") (name "unconnected-(U1-IO3-Pad15)") (class "Default")
      (node (ref "U1") (pin "15") (pinfunction "IO3_15") (pintype "bidirectional+no_connect"))
    )
    (net (code "90") (name "unconnected-(U3-ALERT{slash}RDY-Pad2)") (class "Default")
      (node (ref "U3") (pin "2") (pinfunction "ALERT/RDY_2") (pintype "open_collector+no_connect"))
    )
    (net (code "91") (name "unconnected-(U4-ALERT{slash}RDY-Pad2)") (class "Default")
      (node (ref "U4") (pin "2") (pinfunction "ALERT/RDY_2") (pintype "open_collector+no_connect"))
    )
    (net (code "92") (name "unconnected-(U6-A8-Pad9)") (class "Default")
      (node (ref "U6") (pin "9") (pinfunction "A8_9") (pintype "bidirectional"))
    )
    (net (code "93") (name "unconnected-(U6-B8-Pad12)") (class "Default")
      (node (ref "U6") (pin "12") (pinfunction "B8_12") (pintype "bidirectional"))
    )
  )
)
